# dust_environment_sensor.net
KiCad netlist of a schematic drawn in EAGLE
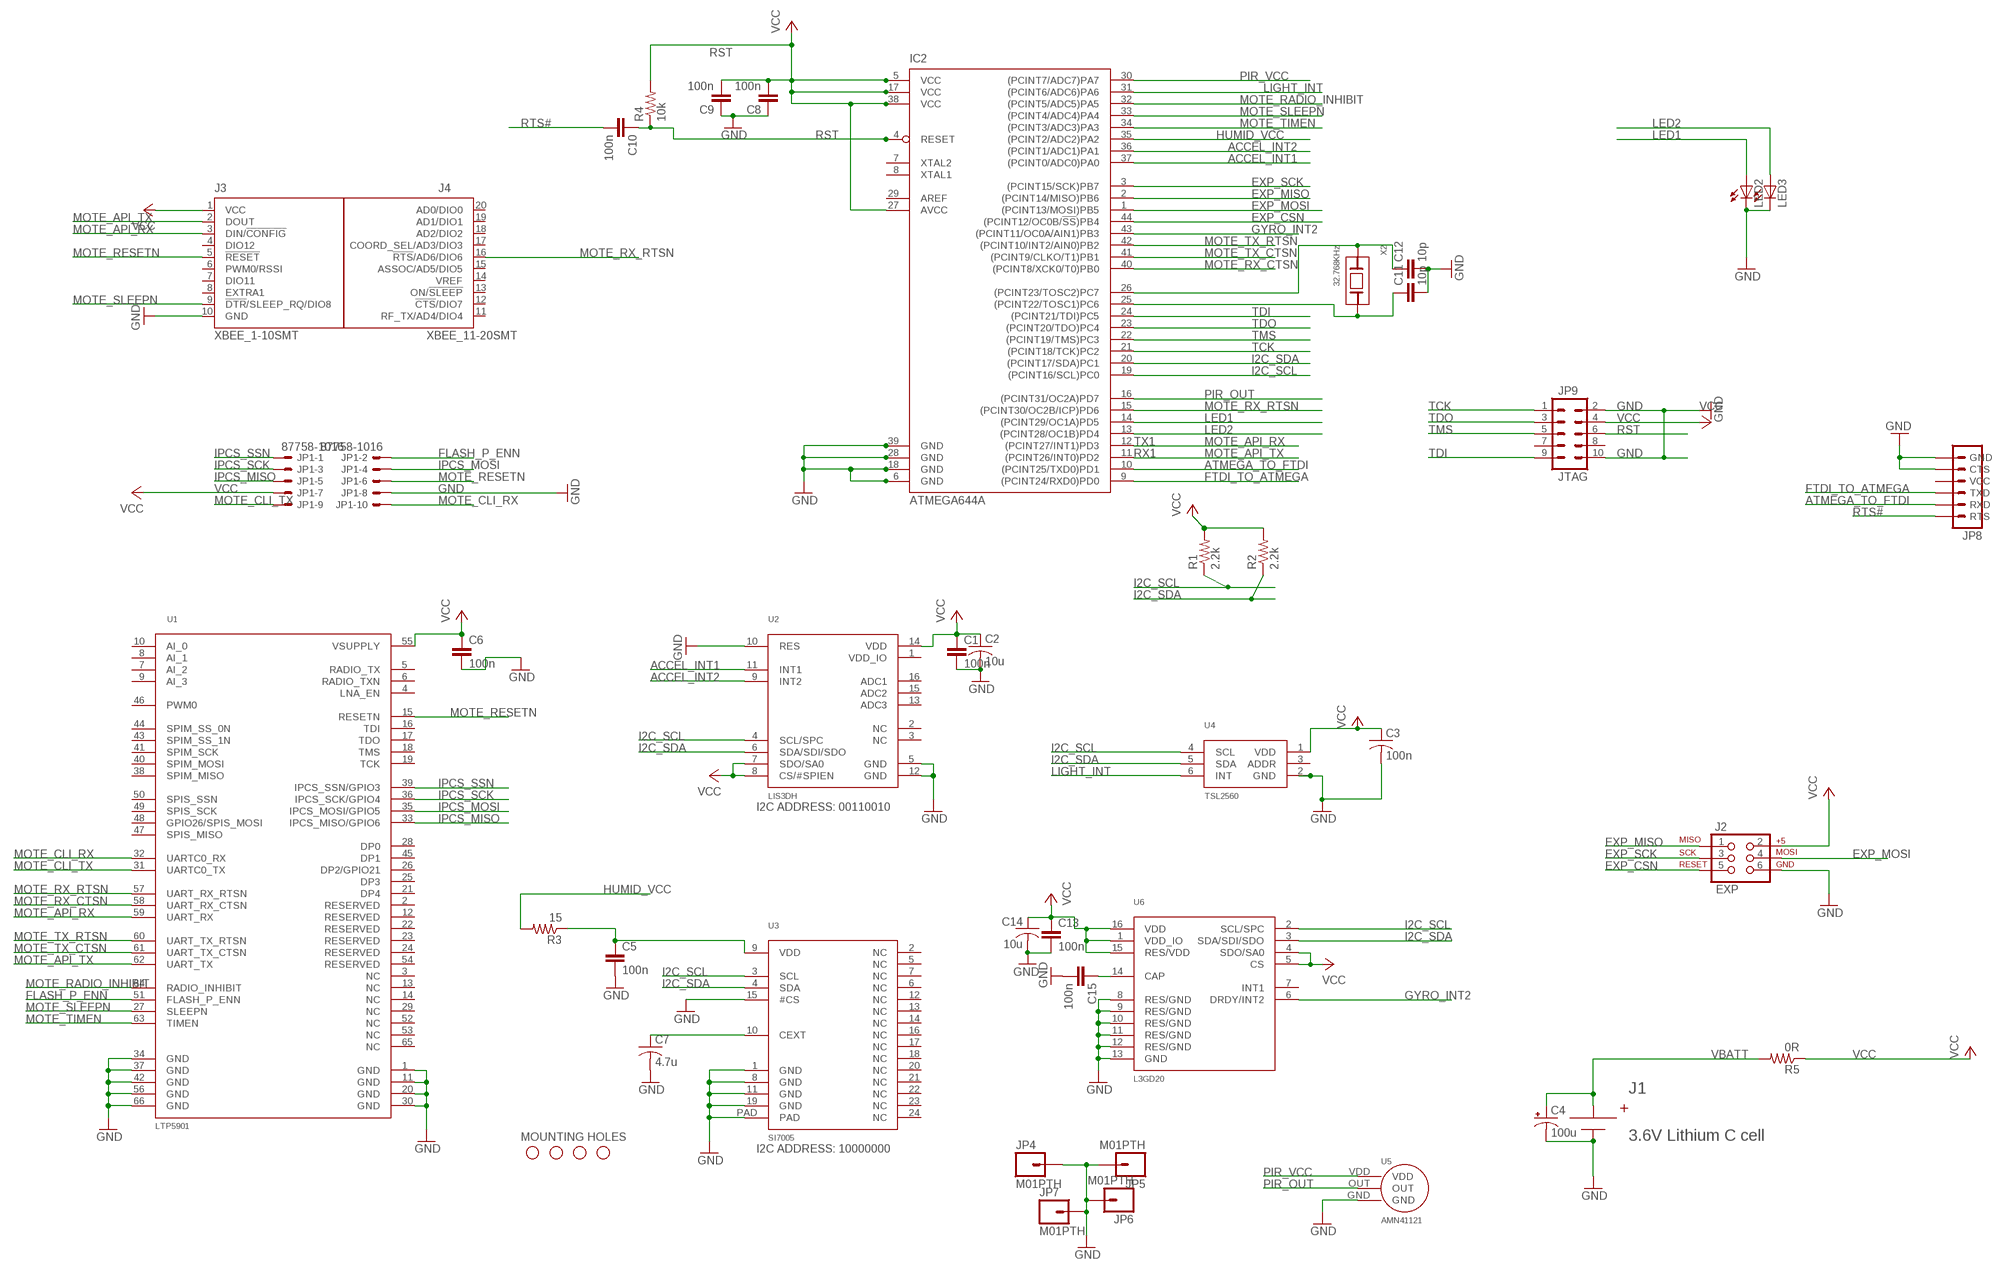
[diagram p0: schematic, sheet 1]

(export (version "E")
  (design (tool "Eeschema 10.0.6"))
  (components
    (comp (ref "C1")
      (value "100n")
      (footprint "eagle-import:C0603")
      (libsource (lib "eagle-import") (part "C-EUC0603"))
    )
    (comp (ref "C2")
      (value "10u")
      (footprint "eagle-import:C0603")
      (libsource (lib "eagle-import") (part "C-USC0603"))
    )
    (comp (ref "C3")
      (value "100n")
      (footprint "eagle-import:C0603")
      (libsource (lib "eagle-import") (part "C-USC0603"))
    )
    (comp (ref "C4")
      (value "100u")
      (footprint "eagle-import:EIA3216-KIT")
      (libsource (lib "eagle-import") (part "CAP_POL1206-KIT"))
    )
    (comp (ref "C5")
      (value "100n")
      (footprint "eagle-import:C0603")
      (libsource (lib "eagle-import") (part "C-EUC0603"))
    )
    (comp (ref "C6")
      (value "100n")
      (footprint "eagle-import:C0603")
      (libsource (lib "eagle-import") (part "C-EUC0603"))
    )
    (comp (ref "C7")
      (value "4.7u")
      (footprint "eagle-import:C0603")
      (libsource (lib "eagle-import") (part "C-USC0603"))
    )
    (comp (ref "C8")
      (value "100n")
      (footprint "eagle-import:C0603")
      (libsource (lib "eagle-import") (part "C-EUC0603"))
    )
    (comp (ref "C9")
      (value "100n")
      (footprint "eagle-import:C0603")
      (libsource (lib "eagle-import") (part "C-EUC0603"))
    )
    (comp (ref "C10")
      (value "100n")
      (footprint "eagle-import:C0603")
      (libsource (lib "eagle-import") (part "C-EUC0603"))
    )
    (comp (ref "C11")
      (value "10p")
      (footprint "eagle-import:C0603")
      (libsource (lib "eagle-import") (part "C-EUC0603"))
    )
    (comp (ref "C12")
      (value "10p")
      (footprint "eagle-import:C0603")
      (libsource (lib "eagle-import") (part "C-EUC0603"))
    )
    (comp (ref "C13")
      (value "100n")
      (footprint "eagle-import:C0603")
      (libsource (lib "eagle-import") (part "C-EUC0603"))
    )
    (comp (ref "C14")
      (value "10u")
      (footprint "eagle-import:C0603")
      (libsource (lib "eagle-import") (part "C-USC0603"))
    )
    (comp (ref "C15")
      (value "100n")
      (footprint "eagle-import:C0603")
      (libsource (lib "eagle-import") (part "C-EUC0603"))
    )
    (comp (ref "IC2")
      (value "ATMEGA644A")
      (footprint "eagle-import:TQFP44")
      (fields (field (name "MPN") "ATMEGA644PV-10AU"))
      (libsource (lib "eagle-import") (part "ATMEGA644A"))
    )
    (comp (ref "J1")
      (value "3.6V Lithium C cell")
      (footprint "eagle-import:BX0036")
      (libsource (lib "eagle-import") (part "BX0036"))
    )
    (comp (ref "J2")
      (value "EXP")
      (footprint "eagle-import:2X3")
      (libsource (lib "eagle-import") (part "AVR_SPI_PRG_6PTH"))
    )
    (comp (ref "J3")
      (value "XBEE_1-10SMT")
      (footprint "eagle-import:XBEE_1-10_SMT")
      (libsource (lib "eagle-import") (part "XBEE_1-10SMT"))
    )
    (comp (ref "J4")
      (value "XBEE_11-20SMT")
      (footprint "eagle-import:XBEE_11-20_SMT")
      (libsource (lib "eagle-import") (part "XBEE_11-20SMT"))
    )
    (comp (ref "JP1")
      (value "87758-1016")
      (footprint "eagle-import:87758-1016")
      (fields (field (name "MF") "MOLEX"))
      (libsource (lib "eagle-import") (part "87758-1016"))
    )
    (comp (ref "JP4")
      (value "M01PTH")
      (footprint "eagle-import:1X01")
      (libsource (lib "eagle-import") (part "M01PTH"))
    )
    (comp (ref "JP5")
      (value "M01PTH")
      (footprint "eagle-import:1X01")
      (libsource (lib "eagle-import") (part "M01PTH"))
    )
    (comp (ref "JP6")
      (value "M01PTH")
      (footprint "eagle-import:1X01")
      (libsource (lib "eagle-import") (part "M01PTH"))
    )
    (comp (ref "JP7")
      (value "M01PTH")
      (footprint "eagle-import:1X01")
      (libsource (lib "eagle-import") (part "M01PTH"))
    )
    (comp (ref "JP8")
      (value "FTDI_CABLESIP")
      (footprint "eagle-import:1X06")
      (libsource (lib "eagle-import") (part "FTDI_CABLESIP"))
    )
    (comp (ref "JP9")
      (value "JTAG")
      (footprint "eagle-import:AVR_ICSP")
      (libsource (lib "eagle-import") (part "M05X2PTH"))
    )
    (comp (ref "LED2")
      (value "LEDCHIPLED_0805")
      (footprint "eagle-import:CHIPLED_0805")
      (libsource (lib "eagle-import") (part "LEDCHIPLED_0805"))
    )
    (comp (ref "LED3")
      (value "LEDCHIPLED_0805")
      (footprint "eagle-import:CHIPLED_0805")
      (libsource (lib "eagle-import") (part "LEDCHIPLED_0805"))
    )
    (comp (ref "R1")
      (value "2.2k")
      (footprint "eagle-import:R0603")
      (libsource (lib "eagle-import") (part "R-US_R0603"))
    )
    (comp (ref "R2")
      (value "2.2k")
      (footprint "eagle-import:R0603")
      (libsource (lib "eagle-import") (part "R-US_R0603"))
    )
    (comp (ref "R3")
      (value "15")
      (footprint "eagle-import:R0603")
      (libsource (lib "eagle-import") (part "R-US_R0603"))
    )
    (comp (ref "R4")
      (value "10k")
      (footprint "eagle-import:R0603")
      (libsource (lib "eagle-import") (part "R-US_R0603"))
    )
    (comp (ref "R5")
      (value "0R")
      (footprint "eagle-import:R0603")
      (libsource (lib "eagle-import") (part "R-US_R0603"))
    )
    (comp (ref "STANDOFF1")
      (value "STAND-OFF")
      (footprint "eagle-import:STAND-OFF")
      (libsource (lib "eagle-import") (part "STAND-OFF"))
    )
    (comp (ref "STANDOFF2")
      (value "STAND-OFF")
      (footprint "eagle-import:STAND-OFF")
      (libsource (lib "eagle-import") (part "STAND-OFF"))
    )
    (comp (ref "STANDOFF3")
      (value "STAND-OFF")
      (footprint "eagle-import:STAND-OFF")
      (libsource (lib "eagle-import") (part "STAND-OFF"))
    )
    (comp (ref "STANDOFF4")
      (value "STAND-OFF")
      (footprint "eagle-import:STAND-OFF")
      (libsource (lib "eagle-import") (part "STAND-OFF"))
    )
    (comp (ref "U1")
      (value "LTP5901")
      (footprint "eagle-import:LTP5901_MODULE")
      (libsource (lib "eagle-import") (part "LTP5901"))
    )
    (comp (ref "U2")
      (value "LIS3DH")
      (footprint "eagle-import:LGA16_ST")
      (libsource (lib "eagle-import") (part "LIS3DH"))
    )
    (comp (ref "U3")
      (value "SI7005")
      (footprint "eagle-import:QFN24_SILICON_LABS")
      (libsource (lib "eagle-import") (part "SI7005"))
    )
    (comp (ref "U4")
      (value "TSL2560")
      (footprint "eagle-import:CL6_TAOS")
      (libsource (lib "eagle-import") (part "TSL2560"))
    )
    (comp (ref "U5")
      (value "AMN41121")
      (footprint "eagle-import:AMN41121")
      (libsource (lib "eagle-import") (part "AMN41121"))
    )
    (comp (ref "U6")
      (value "L3GD20")
      (footprint "eagle-import:LGA16_4X4_ST")
      (libsource (lib "eagle-import") (part "L3GD20"))
    )
    (comp (ref "X2")
      (value "32.768KHz")
      (footprint "eagle-import:ABS07")
      (libsource (lib "eagle-import") (part "XTALABS07"))
    )
  )
  (nets
    (net (code "1") (name "/ACCEL_INT1") (class "Default")
      (node (ref "IC2") (pin "37") (pinfunction "(PCINT0/ADC0)PA0_37") (pintype "bidirectional"))
      (node (ref "U2") (pin "11") (pinfunction "INT1_11") (pintype "bidirectional"))
    )
    (net (code "2") (name "/ACCEL_INT2") (class "Default")
      (node (ref "IC2") (pin "36") (pinfunction "(PCINT1/ADC1)PA1_36") (pintype "bidirectional"))
      (node (ref "U2") (pin "9") (pinfunction "INT2_9") (pintype "bidirectional"))
    )
    (net (code "3") (name "/ATMEGA_TO_FTDI") (class "Default")
      (node (ref "IC2") (pin "10") (pinfunction "(PCINT25/TXD0)PD1_10") (pintype "bidirectional"))
      (node (ref "JP8") (pin "5") (pinfunction "RXD_5") (pintype "passive"))
    )
    (net (code "4") (name "/EXP_CSN") (class "Default")
      (node (ref "IC2") (pin "44") (pinfunction "(PCINT12/OC0B/~{SS})PB4_44") (pintype "bidirectional"))
      (node (ref "J2") (pin "5") (pinfunction "5_5") (pintype "passive"))
    )
    (net (code "5") (name "/EXP_MISO") (class "Default")
      (node (ref "IC2") (pin "2") (pinfunction "(PCINT14/MISO)PB6_2") (pintype "bidirectional"))
      (node (ref "J2") (pin "1") (pinfunction "1_1") (pintype "passive"))
    )
    (net (code "6") (name "/EXP_MOSI") (class "Default")
      (node (ref "IC2") (pin "1") (pinfunction "(PCINT13/MOSI)PB5_1") (pintype "bidirectional"))
      (node (ref "J2") (pin "4") (pinfunction "4_4") (pintype "passive"))
    )
    (net (code "7") (name "/EXP_SCK") (class "Default")
      (node (ref "IC2") (pin "3") (pinfunction "(PCINT15/SCK)PB7_3") (pintype "bidirectional"))
      (node (ref "J2") (pin "3") (pinfunction "3_3") (pintype "passive"))
    )
    (net (code "8") (name "/FLASH_P_ENN") (class "Default")
      (node (ref "JP1") (pin "2") (pinfunction "S_2") (pintype "passive"))
      (node (ref "U1") (pin "51") (pinfunction "FLASH_P_ENN_51") (pintype "bidirectional"))
    )
    (net (code "9") (name "/FTDI_TO_ATMEGA") (class "Default")
      (node (ref "IC2") (pin "9") (pinfunction "(PCINT24/RXD0)PD0_9") (pintype "bidirectional"))
      (node (ref "JP8") (pin "4") (pinfunction "TXD_4") (pintype "passive"))
    )
    (net (code "10") (name "/GYRO_INT2") (class "Default")
      (node (ref "IC2") (pin "43") (pinfunction "(PCINT11/OC0A/AIN1)PB3_43") (pintype "bidirectional"))
      (node (ref "U6") (pin "6") (pinfunction "DRDY/INT2_6") (pintype "bidirectional"))
    )
    (net (code "11") (name "/HUMID_VCC") (class "Default")
      (node (ref "IC2") (pin "35") (pinfunction "(PCINT2/ADC2)PA2_35") (pintype "bidirectional"))
      (node (ref "R3") (pin "2") (pinfunction "2_2") (pintype "passive"))
    )
    (net (code "12") (name "/I2C_SCL") (class "Default")
      (node (ref "IC2") (pin "19") (pinfunction "(PCINT16/SCL)PC0_19") (pintype "output"))
      (node (ref "R1") (pin "1") (pinfunction "1_1") (pintype "passive"))
      (node (ref "U2") (pin "4") (pinfunction "SCL/SPC_4") (pintype "bidirectional"))
      (node (ref "U3") (pin "3") (pinfunction "SCL_3") (pintype "bidirectional"))
      (node (ref "U4") (pin "4") (pinfunction "SCL_4") (pintype "bidirectional"))
      (node (ref "U6") (pin "2") (pinfunction "SCL/SPC_2") (pintype "bidirectional"))
    )
    (net (code "13") (name "/I2C_SDA") (class "Default")
      (node (ref "IC2") (pin "20") (pinfunction "(PCINT17/SDA)PC1_20") (pintype "output"))
      (node (ref "R2") (pin "1") (pinfunction "1_1") (pintype "passive"))
      (node (ref "U2") (pin "6") (pinfunction "SDA/SDI/SDO_6") (pintype "bidirectional"))
      (node (ref "U3") (pin "4") (pinfunction "SDA_4") (pintype "bidirectional"))
      (node (ref "U4") (pin "5") (pinfunction "SDA_5") (pintype "bidirectional"))
      (node (ref "U6") (pin "3") (pinfunction "SDA/SDI/SDO_3") (pintype "bidirectional"))
    )
    (net (code "14") (name "/IPCS_MISO") (class "Default")
      (node (ref "JP1") (pin "5") (pinfunction "S_5") (pintype "passive"))
      (node (ref "U1") (pin "33") (pinfunction "IPCS_MISO/GPIO6_33") (pintype "bidirectional"))
    )
    (net (code "15") (name "/IPCS_MOSI") (class "Default")
      (node (ref "JP1") (pin "4") (pinfunction "S_4") (pintype "passive"))
      (node (ref "U1") (pin "35") (pinfunction "IPCS_MOSI/GPIO5_35") (pintype "bidirectional"))
    )
    (net (code "16") (name "/IPCS_SCK") (class "Default")
      (node (ref "JP1") (pin "3") (pinfunction "S_3") (pintype "passive"))
      (node (ref "U1") (pin "36") (pinfunction "IPCS_SCK/GPIO4_36") (pintype "bidirectional"))
    )
    (net (code "17") (name "/IPCS_SSN") (class "Default")
      (node (ref "JP1") (pin "1") (pinfunction "S_1") (pintype "passive"))
      (node (ref "U1") (pin "39") (pinfunction "IPCS_SSN/GPIO3_39") (pintype "bidirectional"))
    )
    (net (code "18") (name "/LED1") (class "Default")
      (node (ref "IC2") (pin "14") (pinfunction "(PCINT29/OC1A)PD5_14") (pintype "bidirectional"))
      (node (ref "LED2") (pin "A") (pinfunction "A_A") (pintype "passive"))
    )
    (net (code "19") (name "/LED2") (class "Default")
      (node (ref "IC2") (pin "13") (pinfunction "(PCINT28/OC1B)PD4_13") (pintype "bidirectional"))
      (node (ref "LED3") (pin "A") (pinfunction "A_A") (pintype "passive"))
    )
    (net (code "20") (name "/LIGHT_INT") (class "Default")
      (node (ref "IC2") (pin "31") (pinfunction "(PCINT6/ADC6)PA6_31") (pintype "bidirectional"))
      (node (ref "U4") (pin "6") (pinfunction "INT_6") (pintype "bidirectional"))
    )
    (net (code "21") (name "/MOTE_API_RX") (class "Default")
      (node (ref "IC2") (pin "12") (pinfunction "(PCINT27/INT1)PD3_12") (pintype "bidirectional"))
      (node (ref "J3") (pin "3") (pinfunction "DIN/~{CONFIG}_3") (pintype "input"))
      (node (ref "U1") (pin "59") (pinfunction "UART_RX_59") (pintype "bidirectional"))
    )
    (net (code "22") (name "/MOTE_API_TX") (class "Default")
      (node (ref "IC2") (pin "11") (pinfunction "(PCINT26/INT0)PD2_11") (pintype "bidirectional"))
      (node (ref "J3") (pin "2") (pinfunction "DOUT_2") (pintype "output"))
      (node (ref "U1") (pin "62") (pinfunction "UART_TX_62") (pintype "bidirectional"))
    )
    (net (code "23") (name "/MOTE_CLI_RX") (class "Default")
      (node (ref "JP1") (pin "10") (pinfunction "S_10") (pintype "passive"))
      (node (ref "U1") (pin "32") (pinfunction "UARTC0_RX_32") (pintype "bidirectional"))
    )
    (net (code "24") (name "/MOTE_CLI_TX") (class "Default")
      (node (ref "JP1") (pin "9") (pinfunction "S_9") (pintype "passive"))
      (node (ref "U1") (pin "31") (pinfunction "UARTC0_TX_31") (pintype "bidirectional"))
    )
    (net (code "25") (name "/MOTE_RADIO_INHIBIT") (class "Default")
      (node (ref "IC2") (pin "32") (pinfunction "(PCINT5/ADC5)PA5_32") (pintype "bidirectional"))
      (node (ref "U1") (pin "64") (pinfunction "RADIO_INHIBIT_64") (pintype "bidirectional"))
    )
    (net (code "26") (name "/MOTE_RESETN") (class "Default")
      (node (ref "J3") (pin "5") (pinfunction "~{RESET}_5") (pintype "input"))
      (node (ref "JP1") (pin "6") (pinfunction "S_6") (pintype "passive"))
      (node (ref "U1") (pin "15") (pinfunction "RESETN_15") (pintype "bidirectional"))
    )
    (net (code "27") (name "/MOTE_RX_CTSN") (class "Default")
      (node (ref "IC2") (pin "40") (pinfunction "(PCINT8/XCK0/T0)PB0_40") (pintype "bidirectional"))
      (node (ref "U1") (pin "58") (pinfunction "UART_RX_CTSN_58") (pintype "bidirectional"))
    )
    (net (code "28") (name "/MOTE_RX_RTSN") (class "Default")
      (node (ref "IC2") (pin "15") (pinfunction "(PCINT30/OC2B/ICP)PD6_15") (pintype "bidirectional"))
      (node (ref "J4") (pin "16") (pinfunction "~{RTS}/AD6/DIO6_16") (pintype "bidirectional"))
      (node (ref "U1") (pin "57") (pinfunction "UART_RX_RTSN_57") (pintype "bidirectional"))
    )
    (net (code "29") (name "/MOTE_SLEEPN") (class "Default")
      (node (ref "IC2") (pin "33") (pinfunction "(PCINT4/ADC4)PA4_33") (pintype "bidirectional"))
      (node (ref "J3") (pin "9") (pinfunction "~{DTR}/SLEEP_RQ/DIO8_9") (pintype "bidirectional"))
      (node (ref "U1") (pin "27") (pinfunction "SLEEPN_27") (pintype "bidirectional"))
    )
    (net (code "30") (name "/MOTE_TIMEN") (class "Default")
      (node (ref "IC2") (pin "34") (pinfunction "(PCINT3/ADC3)PA3_34") (pintype "bidirectional"))
      (node (ref "U1") (pin "63") (pinfunction "TIMEN_63") (pintype "bidirectional"))
    )
    (net (code "31") (name "/MOTE_TX_CTSN") (class "Default")
      (node (ref "IC2") (pin "41") (pinfunction "(PCINT9/CLKO/T1)PB1_41") (pintype "bidirectional"))
      (node (ref "U1") (pin "61") (pinfunction "UART_TX_CTSN_61") (pintype "bidirectional"))
    )
    (net (code "32") (name "/MOTE_TX_RTSN") (class "Default")
      (node (ref "IC2") (pin "42") (pinfunction "(PCINT10/INT2/AIN0)PB2_42") (pintype "bidirectional"))
      (node (ref "U1") (pin "60") (pinfunction "UART_TX_RTSN_60") (pintype "bidirectional"))
    )
    (net (code "33") (name "/PIR_OUT") (class "Default")
      (node (ref "IC2") (pin "16") (pinfunction "(PCINT31/OC2A)PD7_16") (pintype "bidirectional"))
      (node (ref "U5") (pin "OUT") (pinfunction "OUT_OUT") (pintype "bidirectional"))
    )
    (net (code "34") (name "/PIR_VCC") (class "Default")
      (node (ref "IC2") (pin "30") (pinfunction "(PCINT7/ADC7)PA7_30") (pintype "bidirectional"))
      (node (ref "U5") (pin "VDD") (pinfunction "VDD_VDD") (pintype "bidirectional"))
    )
    (net (code "35") (name "/RST") (class "Default")
      (node (ref "C10") (pin "1") (pinfunction "1_1") (pintype "passive"))
      (node (ref "IC2") (pin "4") (pinfunction "RESET_4") (pintype "input"))
      (node (ref "JP9") (pin "6") (pinfunction "6_6") (pintype "passive"))
      (node (ref "R4") (pin "1") (pinfunction "1_1") (pintype "passive"))
    )
    (net (code "36") (name "/RTS#") (class "Default")
      (node (ref "C10") (pin "2") (pinfunction "2_2") (pintype "passive"))
      (node (ref "JP8") (pin "6") (pinfunction "RTS_6") (pintype "passive"))
    )
    (net (code "37") (name "/TCK") (class "Default")
      (node (ref "IC2") (pin "21") (pinfunction "(PCINT18/TCK)PC2_21") (pintype "output"))
      (node (ref "JP9") (pin "1") (pinfunction "1_1") (pintype "passive"))
    )
    (net (code "38") (name "/TDI") (class "Default")
      (node (ref "IC2") (pin "24") (pinfunction "(PCINT21/TDI)PC5_24") (pintype "output"))
      (node (ref "JP9") (pin "9") (pinfunction "9_9") (pintype "passive"))
    )
    (net (code "39") (name "/TDO") (class "Default")
      (node (ref "IC2") (pin "23") (pinfunction "(PCINT20/TDO)PC4_23") (pintype "output"))
      (node (ref "JP9") (pin "3") (pinfunction "3_3") (pintype "passive"))
    )
    (net (code "40") (name "/TMS") (class "Default")
      (node (ref "IC2") (pin "22") (pinfunction "(PCINT19/TMS)PC3_22") (pintype "output"))
      (node (ref "JP9") (pin "5") (pinfunction "5_5") (pintype "passive"))
    )
    (net (code "41") (name "/VBATT") (class "Default")
      (node (ref "C4") (pin "A") (pinfunction "+_A") (pintype "passive"))
      (node (ref "J1") (pin "POS") (pinfunction "POS_POS") (pintype "bidirectional"))
      (node (ref "R5") (pin "2") (pinfunction "2_2") (pintype "passive"))
    )
    (net (code "42") (name "GND") (class "Default")
      (node (ref "C1") (pin "2") (pinfunction "2_2") (pintype "passive"))
      (node (ref "C11") (pin "2") (pinfunction "2_2") (pintype "passive"))
      (node (ref "C12") (pin "2") (pinfunction "2_2") (pintype "passive"))
      (node (ref "C13") (pin "2") (pinfunction "2_2") (pintype "passive"))
      (node (ref "C14") (pin "2") (pinfunction "2_2") (pintype "passive"))
      (node (ref "C15") (pin "2") (pinfunction "2_2") (pintype "passive"))
      (node (ref "C2") (pin "2") (pinfunction "2_2") (pintype "passive"))
      (node (ref "C3") (pin "2") (pinfunction "2_2") (pintype "passive"))
      (node (ref "C4") (pin "C") (pinfunction "-_C") (pintype "passive"))
      (node (ref "C5") (pin "2") (pinfunction "2_2") (pintype "passive"))
      (node (ref "C6") (pin "2") (pinfunction "2_2") (pintype "passive"))
      (node (ref "C7") (pin "2") (pinfunction "2_2") (pintype "passive"))
      (node (ref "C8") (pin "1") (pinfunction "1_1") (pintype "passive"))
      (node (ref "C9") (pin "1") (pinfunction "1_1") (pintype "passive"))
      (node (ref "IC2") (pin "18") (pinfunction "GND_18") (pintype "power_in"))
      (node (ref "IC2") (pin "28") (pinfunction "GND_28") (pintype "power_in"))
      (node (ref "IC2") (pin "39") (pinfunction "GND_39") (pintype "power_in"))
      (node (ref "IC2") (pin "6") (pinfunction "GND_6") (pintype "power_in"))
      (node (ref "J1") (pin "NEG") (pinfunction "NEG_NEG") (pintype "bidirectional"))
      (node (ref "J2") (pin "6") (pinfunction "6_6") (pintype "passive"))
      (node (ref "J3") (pin "10") (pinfunction "GND_10") (pintype "power_in"))
      (node (ref "JP1") (pin "8") (pinfunction "S_8") (pintype "passive"))
      (node (ref "JP4") (pin "1") (pinfunction "1_1") (pintype "passive"))
      (node (ref "JP5") (pin "1") (pinfunction "1_1") (pintype "passive"))
      (node (ref "JP6") (pin "1") (pinfunction "1_1") (pintype "passive"))
      (node (ref "JP7") (pin "1") (pinfunction "1_1") (pintype "passive"))
      (node (ref "JP8") (pin "1") (pinfunction "GND_1") (pintype "passive"))
      (node (ref "JP8") (pin "2") (pinfunction "CTS_2") (pintype "passive"))
      (node (ref "JP9") (pin "10") (pinfunction "10_10") (pintype "passive"))
      (node (ref "JP9") (pin "2") (pinfunction "2_2") (pintype "passive"))
      (node (ref "LED2") (pin "C") (pinfunction "C_C") (pintype "passive"))
      (node (ref "LED3") (pin "C") (pinfunction "C_C") (pintype "passive"))
      (node (ref "U1") (pin "1") (pinfunction "GND_1") (pintype "bidirectional"))
      (node (ref "U1") (pin "11") (pinfunction "GND_11") (pintype "bidirectional"))
      (node (ref "U1") (pin "20") (pinfunction "GND_20") (pintype "bidirectional"))
      (node (ref "U1") (pin "30") (pinfunction "GND_30") (pintype "bidirectional"))
      (node (ref "U1") (pin "34") (pinfunction "GND_34") (pintype "bidirectional"))
      (node (ref "U1") (pin "37") (pinfunction "GND_37") (pintype "bidirectional"))
      (node (ref "U1") (pin "42") (pinfunction "GND_42") (pintype "bidirectional"))
      (node (ref "U1") (pin "56") (pinfunction "GND_56") (pintype "bidirectional"))
      (node (ref "U1") (pin "66") (pinfunction "GND_66") (pintype "bidirectional"))
      (node (ref "U2") (pin "10") (pinfunction "RES_10") (pintype "bidirectional"))
      (node (ref "U2") (pin "12") (pinfunction "GND_12") (pintype "bidirectional"))
      (node (ref "U2") (pin "5") (pinfunction "GND_5") (pintype "bidirectional"))
      (node (ref "U3") (pin "1") (pinfunction "GND_1") (pintype "bidirectional"))
      (node (ref "U3") (pin "11") (pinfunction "GND_11") (pintype "bidirectional"))
      (node (ref "U3") (pin "15") (pinfunction "#CS_15") (pintype "bidirectional"))
      (node (ref "U3") (pin "19") (pinfunction "GND_19") (pintype "bidirectional"))
      (node (ref "U3") (pin "8") (pinfunction "GND_8") (pintype "bidirectional"))
      (node (ref "U3") (pin "PAD") (pinfunction "PAD_PAD") (pintype "bidirectional"))
      (node (ref "U4") (pin "2") (pinfunction "GND_2") (pintype "bidirectional"))
      (node (ref "U5") (pin "GND") (pinfunction "GND_GND") (pintype "bidirectional"))
      (node (ref "U6") (pin "10") (pinfunction "RES/GND_10") (pintype "bidirectional"))
      (node (ref "U6") (pin "11") (pinfunction "RES/GND_11") (pintype "bidirectional"))
      (node (ref "U6") (pin "12") (pinfunction "RES/GND_12") (pintype "bidirectional"))
      (node (ref "U6") (pin "13") (pinfunction "GND_13") (pintype "bidirectional"))
      (node (ref "U6") (pin "8") (pinfunction "RES/GND_8") (pintype "bidirectional"))
      (node (ref "U6") (pin "9") (pinfunction "RES/GND_9") (pintype "bidirectional"))
    )
    (net (code "43") (name "Net-(IC2-(PCINT22{slash}TOSC1)PC6)") (class "Default")
      (node (ref "C11") (pin "1") (pinfunction "1_1") (pintype "passive"))
      (node (ref "IC2") (pin "25") (pinfunction "(PCINT22/TOSC1)PC6_25") (pintype "output"))
      (node (ref "X2") (pin "2") (pinfunction "B_2") (pintype "bidirectional"))
    )
    (net (code "44") (name "Net-(IC2-(PCINT23{slash}TOSC2)PC7)") (class "Default")
      (node (ref "C12") (pin "1") (pinfunction "1_1") (pintype "passive"))
      (node (ref "IC2") (pin "26") (pinfunction "(PCINT23/TOSC2)PC7_26") (pintype "output"))
      (node (ref "X2") (pin "1") (pinfunction "A_1") (pintype "bidirectional"))
    )
    (net (code "45") (name "Net-(U3-CEXT)") (class "Default")
      (node (ref "C7") (pin "1") (pinfunction "1_1") (pintype "passive"))
      (node (ref "U3") (pin "10") (pinfunction "CEXT_10") (pintype "bidirectional"))
    )
    (net (code "46") (name "Net-(U3-VDD)") (class "Default")
      (node (ref "C5") (pin "1") (pinfunction "1_1") (pintype "passive"))
      (node (ref "R3") (pin "1") (pinfunction "1_1") (pintype "passive"))
      (node (ref "U3") (pin "9") (pinfunction "VDD_9") (pintype "bidirectional"))
    )
    (net (code "47") (name "Net-(U6-CAP)") (class "Default")
      (node (ref "C15") (pin "1") (pinfunction "1_1") (pintype "passive"))
      (node (ref "U6") (pin "14") (pinfunction "CAP_14") (pintype "bidirectional"))
    )
    (net (code "48") (name "VCC") (class "Default")
      (node (ref "C1") (pin "1") (pinfunction "1_1") (pintype "passive"))
      (node (ref "C13") (pin "1") (pinfunction "1_1") (pintype "passive"))
      (node (ref "C14") (pin "1") (pinfunction "1_1") (pintype "passive"))
      (node (ref "C2") (pin "1") (pinfunction "1_1") (pintype "passive"))
      (node (ref "C3") (pin "1") (pinfunction "1_1") (pintype "passive"))
      (node (ref "C6") (pin "1") (pinfunction "1_1") (pintype "passive"))
      (node (ref "C8") (pin "2") (pinfunction "2_2") (pintype "passive"))
      (node (ref "C9") (pin "2") (pinfunction "2_2") (pintype "passive"))
      (node (ref "IC2") (pin "17") (pinfunction "VCC_17") (pintype "power_in"))
      (node (ref "IC2") (pin "27") (pinfunction "AVCC_27") (pintype "power_in"))
      (node (ref "IC2") (pin "38") (pinfunction "VCC_38") (pintype "power_in"))
      (node (ref "IC2") (pin "5") (pinfunction "VCC_5") (pintype "power_in"))
      (node (ref "J2") (pin "2") (pinfunction "2_2") (pintype "passive"))
      (node (ref "J3") (pin "1") (pinfunction "VCC_1") (pintype "power_in"))
      (node (ref "JP1") (pin "7") (pinfunction "S_7") (pintype "passive"))
      (node (ref "JP9") (pin "4") (pinfunction "4_4") (pintype "passive"))
      (node (ref "R1") (pin "2") (pinfunction "2_2") (pintype "passive"))
      (node (ref "R2") (pin "2") (pinfunction "2_2") (pintype "passive"))
      (node (ref "R4") (pin "2") (pinfunction "2_2") (pintype "passive"))
      (node (ref "R5") (pin "1") (pinfunction "1_1") (pintype "passive"))
      (node (ref "U1") (pin "55") (pinfunction "VSUPPLY_55") (pintype "bidirectional"))
      (node (ref "U2") (pin "14") (pinfunction "VDD_14") (pintype "bidirectional"))
      (node (ref "U2") (pin "7") (pinfunction "SDO/SA0_7") (pintype "bidirectional"))
      (node (ref "U2") (pin "8") (pinfunction "CS/#SPIEN_8") (pintype "bidirectional"))
      (node (ref "U4") (pin "1") (pinfunction "VDD_1") (pintype "bidirectional"))
      (node (ref "U6") (pin "1") (pinfunction "VDD_IO_1") (pintype "bidirectional"))
      (node (ref "U6") (pin "15") (pinfunction "RES/VDD_15") (pintype "bidirectional"))
      (node (ref "U6") (pin "16") (pinfunction "VDD_16") (pintype "bidirectional"))
      (node (ref "U6") (pin "4") (pinfunction "SDO/SA0_4") (pintype "bidirectional"))
      (node (ref "U6") (pin "5") (pinfunction "CS_5") (pintype "bidirectional"))
    )
    (net (code "49") (name "unconnected-(IC2-AREF-Pad29)") (class "Default")
      (node (ref "IC2") (pin "29") (pinfunction "AREF_29") (pintype "passive"))
    )
    (net (code "50") (name "unconnected-(IC2-XTAL1-Pad8)") (class "Default")
      (node (ref "IC2") (pin "8") (pinfunction "XTAL1_8") (pintype "bidirectional"))
    )
    (net (code "51") (name "unconnected-(IC2-XTAL2-Pad7)") (class "Default")
      (node (ref "IC2") (pin "7") (pinfunction "XTAL2_7") (pintype "bidirectional"))
    )
    (net (code "52") (name "unconnected-(J3-DIO11-Pad7)") (class "Default")
      (node (ref "J3") (pin "7") (pinfunction "DIO11_7") (pintype "output"))
    )
    (net (code "53") (name "unconnected-(J3-DIO12-Pad4)") (class "Default")
      (node (ref "J3") (pin "4") (pinfunction "DIO12_4") (pintype "bidirectional"))
    )
    (net (code "54") (name "unconnected-(J3-EXTRA1-Pad8)") (class "Default")
      (node (ref "J3") (pin "8") (pinfunction "EXTRA1_8") (pintype "bidirectional"))
    )
    (net (code "55") (name "unconnected-(J3-PWM0{slash}RSSI-Pad6)") (class "Default")
      (node (ref "J3") (pin "6") (pinfunction "PWM0/RSSI_6") (pintype "output"))
    )
    (net (code "56") (name "unconnected-(J4-AD0{slash}DIO0-Pad20)") (class "Default")
      (node (ref "J4") (pin "20") (pinfunction "AD0/DIO0_20") (pintype "bidirectional"))
    )
    (net (code "57") (name "unconnected-(J4-AD1{slash}DIO1-Pad19)") (class "Default")
      (node (ref "J4") (pin "19") (pinfunction "AD1/DIO1_19") (pintype "bidirectional"))
    )
    (net (code "58") (name "unconnected-(J4-AD2{slash}DIO2-Pad18)") (class "Default")
      (node (ref "J4") (pin "18") (pinfunction "AD2/DIO2_18") (pintype "bidirectional"))
    )
    (net (code "59") (name "unconnected-(J4-ASSOC{slash}AD5{slash}DIO5-Pad15)") (class "Default")
      (node (ref "J4") (pin "15") (pinfunction "ASSOC/AD5/DIO5_15") (pintype "bidirectional"))
    )
    (net (code "60") (name "unconnected-(J4-COORD_SEL{slash}AD3{slash}DIO3-Pad17)") (class "Default")
      (node (ref "J4") (pin "17") (pinfunction "COORD_SEL/AD3/DIO3_17") (pintype "bidirectional"))
    )
    (net (code "61") (name "unconnected-(J4-ON{slash}~{SLEEP}-Pad13)") (class "Default")
      (node (ref "J4") (pin "13") (pinfunction "ON/~{SLEEP}_13") (pintype "output"))
    )
    (net (code "62") (name "unconnected-(J4-RF_TX{slash}AD4{slash}DIO4-Pad11)") (class "Default")
      (node (ref "J4") (pin "11") (pinfunction "RF_TX/AD4/DIO4_11") (pintype "bidirectional"))
    )
    (net (code "63") (name "unconnected-(J4-VREF-Pad14)") (class "Default")
      (node (ref "J4") (pin "14") (pinfunction "VREF_14") (pintype "input"))
    )
    (net (code "64") (name "unconnected-(J4-~{CTS}{slash}DIO7-Pad12)") (class "Default")
      (node (ref "J4") (pin "12") (pinfunction "~{CTS}/DIO7_12") (pintype "bidirectional"))
    )
    (net (code "65") (name "unconnected-(JP8-VCC-Pad3)") (class "Default")
      (node (ref "JP8") (pin "3") (pinfunction "VCC_3") (pintype "passive"))
    )
    (net (code "66") (name "unconnected-(JP9-Pad7)") (class "Default")
      (node (ref "JP9") (pin "7") (pinfunction "7_7") (pintype "passive"))
    )
    (net (code "67") (name "unconnected-(JP9-Pad8)") (class "Default")
      (node (ref "JP9") (pin "8") (pinfunction "8_8") (pintype "passive"))
    )
    (net (code "68") (name "unconnected-(U1-AI_0-Pad10)") (class "Default")
      (node (ref "U1") (pin "10") (pinfunction "AI_0_10") (pintype "bidirectional"))
    )
    (net (code "69") (name "unconnected-(U1-AI_1-Pad8)") (class "Default")
      (node (ref "U1") (pin "8") (pinfunction "AI_1_8") (pintype "bidirectional"))
    )
    (net (code "70") (name "unconnected-(U1-AI_2-Pad7)") (class "Default")
      (node (ref "U1") (pin "7") (pinfunction "AI_2_7") (pintype "bidirectional"))
    )
    (net (code "71") (name "unconnected-(U1-AI_3-Pad9)") (class "Default")
      (node (ref "U1") (pin "9") (pinfunction "AI_3_9") (pintype "bidirectional"))
    )
    (net (code "72") (name "unconnected-(U1-DP0-Pad28)") (class "Default")
      (node (ref "U1") (pin "28") (pinfunction "DP0_28") (pintype "bidirectional"))
    )
    (net (code "73") (name "unconnected-(U1-DP1-Pad45)") (class "Default")
      (node (ref "U1") (pin "45") (pinfunction "DP1_45") (pintype "bidirectional"))
    )
    (net (code "74") (name "unconnected-(U1-DP2{slash}GPIO21-Pad26)") (class "Default")
      (node (ref "U1") (pin "26") (pinfunction "DP2/GPIO21_26") (pintype "bidirectional"))
    )
    (net (code "75") (name "unconnected-(U1-DP3-Pad25)") (class "Default")
      (node (ref "U1") (pin "25") (pinfunction "DP3_25") (pintype "bidirectional"))
    )
    (net (code "76") (name "unconnected-(U1-DP4-Pad21)") (class "Default")
      (node (ref "U1") (pin "21") (pinfunction "DP4_21") (pintype "bidirectional"))
    )
    (net (code "77") (name "unconnected-(U1-GPIO26{slash}SPIS_MOSI-Pad48)") (class "Default")
      (node (ref "U1") (pin "48") (pinfunction "GPIO26/SPIS_MOSI_48") (pintype "bidirectional"))
    )
    (net (code "78") (name "unconnected-(U1-LNA_EN-Pad4)") (class "Default")
      (node (ref "U1") (pin "4") (pinfunction "LNA_EN_4") (pintype "bidirectional"))
    )
    (net (code "79") (name "unconnected-(U1-NC-Pad3)") (class "Default")
      (node (ref "U1") (pin "3") (pinfunction "NC_3") (pintype "bidirectional"))
    )
    (net (code "80") (name "unconnected-(U1-NC-Pad13)") (class "Default")
      (node (ref "U1") (pin "13") (pinfunction "NC_13") (pintype "bidirectional"))
    )
    (net (code "81") (name "unconnected-(U1-NC-Pad14)") (class "Default")
      (node (ref "U1") (pin "14") (pinfunction "NC_14") (pintype "bidirectional"))
    )
    (net (code "82") (name "unconnected-(U1-NC-Pad29)") (class "Default")
      (node (ref "U1") (pin "29") (pinfunction "NC_29") (pintype "bidirectional"))
    )
    (net (code "83") (name "unconnected-(U1-NC-Pad52)") (class "Default")
      (node (ref "U1") (pin "52") (pinfunction "NC_52") (pintype "bidirectional"))
    )
    (net (code "84") (name "unconnected-(U1-NC-Pad53)") (class "Default")
      (node (ref "U1") (pin "53") (pinfunction "NC_53") (pintype "bidirectional"))
    )
    (net (code "85") (name "unconnected-(U1-NC-Pad65)") (class "Default")
      (node (ref "U1") (pin "65") (pinfunction "NC_65") (pintype "bidirectional"))
    )
    (net (code "86") (name "unconnected-(U1-PWM0-Pad46)") (class "Default")
      (node (ref "U1") (pin "46") (pinfunction "PWM0_46") (pintype "bidirectional"))
    )
    (net (code "87") (name "unconnected-(U1-RADIO_TX-Pad5)") (class "Default")
      (node (ref "U1") (pin "5") (pinfunction "RADIO_TX_5") (pintype "bidirectional"))
    )
    (net (code "88") (name "unconnected-(U1-RADIO_TXN-Pad6)") (class "Default")
      (node (ref "U1") (pin "6") (pinfunction "RADIO_TXN_6") (pintype "bidirectional"))
    )
    (net (code "89") (name "unconnected-(U1-RESERVED-Pad2)") (class "Default")
      (node (ref "U1") (pin "2") (pinfunction "RESERVED_2") (pintype "bidirectional"))
    )
    (net (code "90") (name "unconnected-(U1-RESERVED-Pad12)") (class "Default")
      (node (ref "U1") (pin "12") (pinfunction "RESERVED_12") (pintype "bidirectional"))
    )
    (net (code "91") (name "unconnected-(U1-RESERVED-Pad22)") (class "Default")
      (node (ref "U1") (pin "22") (pinfunction "RESERVED_22") (pintype "bidirectional"))
    )
    (net (code "92") (name "unconnected-(U1-RESERVED-Pad23)") (class "Default")
      (node (ref "U1") (pin "23") (pinfunction "RESERVED_23") (pintype "bidirectional"))
    )
    (net (code "93") (name "unconnected-(U1-RESERVED-Pad24)") (class "Default")
      (node (ref "U1") (pin "24") (pinfunction "RESERVED_24") (pintype "bidirectional"))
    )
    (net (code "94") (name "unconnected-(U1-RESERVED-Pad54)") (class "Default")
      (node (ref "U1") (pin "54") (pinfunction "RESERVED_54") (pintype "bidirectional"))
    )
    (net (code "95") (name "unconnected-(U1-SPIM_MISO-Pad38)") (class "Default")
      (node (ref "U1") (pin "38") (pinfunction "SPIM_MISO_38") (pintype "bidirectional"))
    )
    (net (code "96") (name "unconnected-(U1-SPIM_MOSI-Pad40)") (class "Default")
      (node (ref "U1") (pin "40") (pinfunction "SPIM_MOSI_40") (pintype "bidirectional"))
    )
    (net (code "97") (name "unconnected-(U1-SPIM_SCK-Pad41)") (class "Default")
      (node (ref "U1") (pin "41") (pinfunction "SPIM_SCK_41") (pintype "bidirectional"))
    )
    (net (code "98") (name "unconnected-(U1-SPIM_SS_0N-Pad44)") (class "Default")
      (node (ref "U1") (pin "44") (pinfunction "SPIM_SS_0N_44") (pintype "bidirectional"))
    )
    (net (code "99") (name "unconnected-(U1-SPIM_SS_1N-Pad43)") (class "Default")
      (node (ref "U1") (pin "43") (pinfunction "SPIM_SS_1N_43") (pintype "bidirectional"))
    )
    (net (code "100") (name "unconnected-(U1-SPIS_MISO-Pad47)") (class "Default")
      (node (ref "U1") (pin "47") (pinfunction "SPIS_MISO_47") (pintype "bidirectional"))
    )
    (net (code "101") (name "unconnected-(U1-SPIS_SCK-Pad49)") (class "Default")
      (node (ref "U1") (pin "49") (pinfunction "SPIS_SCK_49") (pintype "bidirectional"))
    )
    (net (code "102") (name "unconnected-(U1-SPIS_SSN-Pad50)") (class "Default")
      (node (ref "U1") (pin "50") (pinfunction "SPIS_SSN_50") (pintype "bidirectional"))
    )
    (net (code "103") (name "unconnected-(U1-TCK-Pad19)") (class "Default")
      (node (ref "U1") (pin "19") (pinfunction "TCK_19") (pintype "bidirectional"))
    )
    (net (code "104") (name "unconnected-(U1-TDI-Pad16)") (class "Default")
      (node (ref "U1") (pin "16") (pinfunction "TDI_16") (pintype "bidirectional"))
    )
    (net (code "105") (name "unconnected-(U1-TDO-Pad17)") (class "Default")
      (node (ref "U1") (pin "17") (pinfunction "TDO_17") (pintype "bidirectional"))
    )
    (net (code "106") (name "unconnected-(U1-TMS-Pad18)") (class "Default")
      (node (ref "U1") (pin "18") (pinfunction "TMS_18") (pintype "bidirectional"))
    )
    (net (code "107") (name "unconnected-(U2-ADC1-Pad16)") (class "Default")
      (node (ref "U2") (pin "16") (pinfunction "ADC1_16") (pintype "bidirectional"))
    )
    (net (code "108") (name "unconnected-(U2-ADC2-Pad15)") (class "Default")
      (node (ref "U2") (pin "15") (pinfunction "ADC2_15") (pintype "bidirectional"))
    )
    (net (code "109") (name "unconnected-(U2-ADC3-Pad13)") (class "Default")
      (node (ref "U2") (pin "13") (pinfunction "ADC3_13") (pintype "bidirectional"))
    )
    (net (code "110") (name "unconnected-(U2-NC-Pad2)") (class "Default")
      (node (ref "U2") (pin "2") (pinfunction "NC_2") (pintype "bidirectional"))
    )
    (net (code "111") (name "unconnected-(U2-NC-Pad3)") (class "Default")
      (node (ref "U2") (pin "3") (pinfunction "NC_3") (pintype "bidirectional"))
    )
    (net (code "112") (name "unconnected-(U2-VDD_IO-Pad1)") (class "Default")
      (node (ref "U2") (pin "1") (pinfunction "VDD_IO_1") (pintype "bidirectional"))
    )
    (net (code "113") (name "unconnected-(U3-NC-Pad2)") (class "Default")
      (node (ref "U3") (pin "2") (pinfunction "NC_2") (pintype "bidirectional"))
    )
    (net (code "114") (name "unconnected-(U3-NC-Pad5)") (class "Default")
      (node (ref "U3") (pin "5") (pinfunction "NC_5") (pintype "bidirectional"))
    )
    (net (code "115") (name "unconnected-(U3-NC-Pad6)") (class "Default")
      (node (ref "U3") (pin "6") (pinfunction "NC_6") (pintype "bidirectional"))
    )
    (net (code "116") (name "unconnected-(U3-NC-Pad7)") (class "Default")
      (node (ref "U3") (pin "7") (pinfunction "NC_7") (pintype "bidirectional"))
    )
    (net (code "117") (name "unconnected-(U3-NC-Pad12)") (class "Default")
      (node (ref "U3") (pin "12") (pinfunction "NC_12") (pintype "bidirectional"))
    )
    (net (code "118") (name "unconnected-(U3-NC-Pad13)") (class "Default")
      (node (ref "U3") (pin "13") (pinfunction "NC_13") (pintype "bidirectional"))
    )
    (net (code "119") (name "unconnected-(U3-NC-Pad14)") (class "Default")
      (node (ref "U3") (pin "14") (pinfunction "NC_14") (pintype "bidirectional"))
    )
    (net (code "120") (name "unconnected-(U3-NC-Pad16)") (class "Default")
      (node (ref "U3") (pin "16") (pinfunction "NC_16") (pintype "bidirectional"))
    )
    (net (code "121") (name "unconnected-(U3-NC-Pad17)") (class "Default")
      (node (ref "U3") (pin "17") (pinfunction "NC_17") (pintype "bidirectional"))
    )
    (net (code "122") (name "unconnected-(U3-NC-Pad18)") (class "Default")
      (node (ref "U3") (pin "18") (pinfunction "NC_18") (pintype "bidirectional"))
    )
    (net (code "123") (name "unconnected-(U3-NC-Pad20)") (class "Default")
      (node (ref "U3") (pin "20") (pinfunction "NC_20") (pintype "bidirectional"))
    )
    (net (code "124") (name "unconnected-(U3-NC-Pad21)") (class "Default")
      (node (ref "U3") (pin "21") (pinfunction "NC_21") (pintype "bidirectional"))
    )
    (net (code "125") (name "unconnected-(U3-NC-Pad22)") (class "Default")
      (node (ref "U3") (pin "22") (pinfunction "NC_22") (pintype "bidirectional"))
    )
    (net (code "126") (name "unconnected-(U3-NC-Pad23)") (class "Default")
      (node (ref "U3") (pin "23") (pinfunction "NC_23") (pintype "bidirectional"))
    )
    (net (code "127") (name "unconnected-(U3-NC-Pad24)") (class "Default")
      (node (ref "U3") (pin "24") (pinfunction "NC_24") (pintype "bidirectional"))
    )
    (net (code "128") (name "unconnected-(U4-ADDR-Pad3)") (class "Default")
      (node (ref "U4") (pin "3") (pinfunction "ADDR_3") (pintype "bidirectional"))
    )
    (net (code "129") (name "unconnected-(U6-INT1-Pad7)") (class "Default")
      (node (ref "U6") (pin "7") (pinfunction "INT1_7") (pintype "bidirectional"))
    )
  )
)
